# MRF24J40MA_SHIELD.net
KiCad netlist of a schematic drawn in Altium Designer
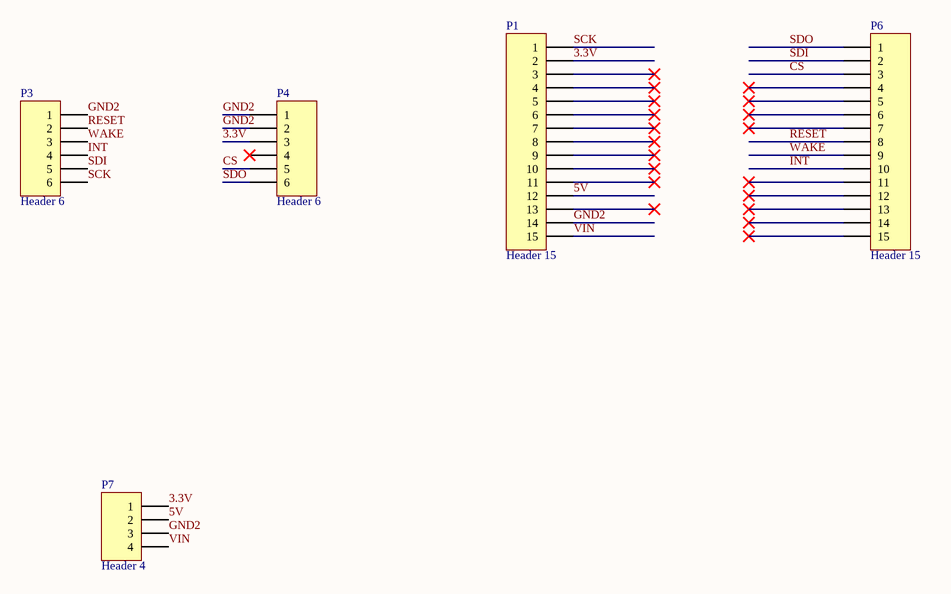
[diagram p0: MRF24J40MA_SHIELD.SchDoc]

(export (version "E")
  (design (tool "Eeschema 10.0.6"))
  (components
    (comp (ref "P1")
      (value "Header 15")
      (footprint "HDR1X15")
      (description "Header, 15-Pin")
      (fields (field (name "PUBLISHER") "Altium Limited"))
      (libsource (lib "Miscellaneous Connectors") (part "Header 15"))
    )
    (comp (ref "P3")
      (value "Header 6")
      (footprint "HDR1X6")
      (description "Header, 6-Pin")
      (fields (field (name "PUBLISHER") "Altium Limited"))
      (libsource (lib "") (part "Header 6_1"))
    )
    (comp (ref "P4")
      (value "Header 6")
      (footprint "HDR1X6")
      (description "Header, 6-Pin")
      (fields (field (name "PUBLISHER") "Altium Limited"))
      (libsource (lib "Miscellaneous Connectors") (part "Header 6"))
    )
    (comp (ref "P6")
      (value "Header 15")
      (footprint "HDR1X15")
      (description "Header, 15-Pin")
      (fields (field (name "PUBLISHER") "Altium Limited"))
      (libsource (lib "") (part "Header 15_1"))
    )
    (comp (ref "P7")
      (value "Header 4")
      (footprint "HDR1X4")
      (description "Header, 4-Pin")
      (fields (field (name "PUBLISHER") "Altium Limited"))
      (libsource (lib "Miscellaneous Connectors") (part "Header 4"))
    )
  )
  (nets
    (net (code "1") (name "/3.3V") (class "Default")
      (node (ref "P1") (pin "2") (pinfunction "2_2") (pintype "passive"))
      (node (ref "P4") (pin "3") (pinfunction "3_3") (pintype "passive"))
      (node (ref "P7") (pin "1") (pinfunction "1_1") (pintype "passive"))
    )
    (net (code "2") (name "/5V") (class "Default")
      (node (ref "P1") (pin "12") (pinfunction "12_12") (pintype "passive"))
      (node (ref "P7") (pin "2") (pinfunction "2_2") (pintype "passive"))
    )
    (net (code "3") (name "/CS") (class "Default")
      (node (ref "P4") (pin "5") (pinfunction "5_5") (pintype "passive"))
      (node (ref "P6") (pin "3") (pinfunction "3_3") (pintype "passive"))
    )
    (net (code "4") (name "/GND2") (class "Default")
      (node (ref "P1") (pin "14") (pinfunction "14_14") (pintype "passive"))
      (node (ref "P3") (pin "1") (pinfunction "1_1") (pintype "passive"))
      (node (ref "P4") (pin "1") (pinfunction "1_1") (pintype "passive"))
      (node (ref "P4") (pin "2") (pinfunction "2_2") (pintype "passive"))
      (node (ref "P7") (pin "3") (pinfunction "3_3") (pintype "passive"))
    )
    (net (code "5") (name "/INT") (class "Default")
      (node (ref "P3") (pin "4") (pinfunction "4_4") (pintype "passive"))
      (node (ref "P6") (pin "10") (pinfunction "10_10") (pintype "passive"))
    )
    (net (code "6") (name "/RESET") (class "Default")
      (node (ref "P3") (pin "2") (pinfunction "2_2") (pintype "passive"))
      (node (ref "P6") (pin "8") (pinfunction "8_8") (pintype "passive"))
    )
    (net (code "7") (name "/SCK") (class "Default")
      (node (ref "P1") (pin "1") (pinfunction "1_1") (pintype "passive"))
      (node (ref "P3") (pin "6") (pinfunction "6_6") (pintype "passive"))
    )
    (net (code "8") (name "/SDI") (class "Default")
      (node (ref "P3") (pin "5") (pinfunction "5_5") (pintype "passive"))
      (node (ref "P6") (pin "2") (pinfunction "2_2") (pintype "passive"))
    )
    (net (code "9") (name "/SDO") (class "Default")
      (node (ref "P4") (pin "6") (pinfunction "6_6") (pintype "passive"))
      (node (ref "P6") (pin "1") (pinfunction "1_1") (pintype "passive"))
    )
    (net (code "10") (name "/VIN") (class "Default")
      (node (ref "P1") (pin "15") (pinfunction "15_15") (pintype "passive"))
      (node (ref "P7") (pin "4") (pinfunction "4_4") (pintype "passive"))
    )
    (net (code "11") (name "/WAKE") (class "Default")
      (node (ref "P3") (pin "3") (pinfunction "3_3") (pintype "passive"))
      (node (ref "P6") (pin "9") (pinfunction "9_9") (pintype "passive"))
    )
    (net (code "12") (name "unconnected-(P1-Pad3)") (class "Default")
      (node (ref "P1") (pin "3") (pinfunction "3_3") (pintype "passive+no_connect"))
    )
    (net (code "13") (name "unconnected-(P1-Pad4)") (class "Default")
      (node (ref "P1") (pin "4") (pinfunction "4_4") (pintype "passive+no_connect"))
    )
    (net (code "14") (name "unconnected-(P1-Pad5)") (class "Default")
      (node (ref "P1") (pin "5") (pinfunction "5_5") (pintype "passive+no_connect"))
    )
    (net (code "15") (name "unconnected-(P1-Pad6)") (class "Default")
      (node (ref "P1") (pin "6") (pinfunction "6_6") (pintype "passive+no_connect"))
    )
    (net (code "16") (name "unconnected-(P1-Pad7)") (class "Default")
      (node (ref "P1") (pin "7") (pinfunction "7_7") (pintype "passive+no_connect"))
    )
    (net (code "17") (name "unconnected-(P1-Pad8)") (class "Default")
      (node (ref "P1") (pin "8") (pinfunction "8_8") (pintype "passive+no_connect"))
    )
    (net (code "18") (name "unconnected-(P1-Pad9)") (class "Default")
      (node (ref "P1") (pin "9") (pinfunction "9_9") (pintype "passive+no_connect"))
    )
    (net (code "19") (name "unconnected-(P1-Pad10)") (class "Default")
      (node (ref "P1") (pin "10") (pinfunction "10_10") (pintype "passive+no_connect"))
    )
    (net (code "20") (name "unconnected-(P1-Pad11)") (class "Default")
      (node (ref "P1") (pin "11") (pinfunction "11_11") (pintype "passive+no_connect"))
    )
    (net (code "21") (name "unconnected-(P1-Pad13)") (class "Default")
      (node (ref "P1") (pin "13") (pinfunction "13_13") (pintype "passive+no_connect"))
    )
    (net (code "22") (name "unconnected-(P4-Pad4)") (class "Default")
      (node (ref "P4") (pin "4") (pinfunction "4_4") (pintype "passive+no_connect"))
    )
    (net (code "23") (name "unconnected-(P6-Pad4)") (class "Default")
      (node (ref "P6") (pin "4") (pinfunction "4_4") (pintype "passive+no_connect"))
    )
    (net (code "24") (name "unconnected-(P6-Pad5)") (class "Default")
      (node (ref "P6") (pin "5") (pinfunction "5_5") (pintype "passive+no_connect"))
    )
    (net (code "25") (name "unconnected-(P6-Pad6)") (class "Default")
      (node (ref "P6") (pin "6") (pinfunction "6_6") (pintype "passive+no_connect"))
    )
    (net (code "26") (name "unconnected-(P6-Pad7)") (class "Default")
      (node (ref "P6") (pin "7") (pinfunction "7_7") (pintype "passive+no_connect"))
    )
    (net (code "27") (name "unconnected-(P6-Pad11)") (class "Default")
      (node (ref "P6") (pin "11") (pinfunction "11_11") (pintype "passive+no_connect"))
    )
    (net (code "28") (name "unconnected-(P6-Pad12)") (class "Default")
      (node (ref "P6") (pin "12") (pinfunction "12_12") (pintype "passive+no_connect"))
    )
    (net (code "29") (name "unconnected-(P6-Pad13)") (class "Default")
      (node (ref "P6") (pin "13") (pinfunction "13_13") (pintype "passive+no_connect"))
    )
    (net (code "30") (name "unconnected-(P6-Pad14)") (class "Default")
      (node (ref "P6") (pin "14") (pinfunction "14_14") (pintype "passive+no_connect"))
    )
    (net (code "31") (name "unconnected-(P6-Pad15)") (class "Default")
      (node (ref "P6") (pin "15") (pinfunction "15_15") (pintype "passive+no_connect"))
    )
  )
)
